# INPUT.net
KiCad netlist of a schematic drawn in Altium Designer
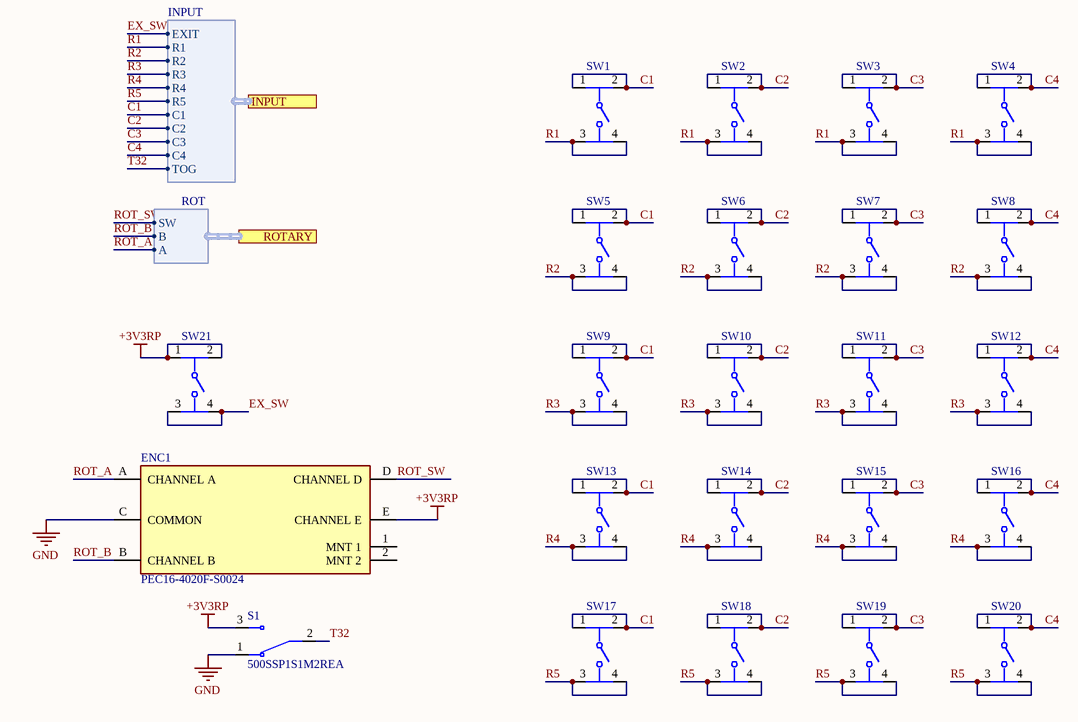
[diagram p0: INPUT.SchDoc]

(export (version "E")
  (design (tool "Eeschema 10.0.6"))
  (components
    (comp (ref "ENC1")
      (value "PEC16-4020F-S0024")
      (footprint "FP-PEC16-4020F-S0024-MFG")
      (description "ROTARY ENCODER MECHANICAL 24PPR")
      (libsource (lib "Components - 05.08.25 - 14.12") (part "CMP-07421-000008-1"))
    )
    (comp (ref "S1")
      (value "500SSP1S1M2REA")
      (footprint "SW_500SSP1S1M2REA")
      (libsource (lib "500SSP1S1M2REA") (part "500SSP1S1M2REA"))
    )
    (comp (ref "SW1")
      (value "MJTP1212A")
      (footprint "FP-MJTP1212A-MFG")
      (description "SWITCH TACTILE SPST-NO 0.05A 12V")
      (libsource (lib "Components - 05.08.25 - 14.03") (part "CMP-47024-000003-1"))
    )
    (comp (ref "SW2")
      (value "MJTP1212A")
      (footprint "FP-MJTP1212A-MFG")
      (description "SWITCH TACTILE SPST-NO 0.05A 12V")
      (libsource (lib "Components - 05.08.25 - 14.03") (part "CMP-47024-000003-1"))
    )
    (comp (ref "SW3")
      (value "MJTP1212A")
      (footprint "FP-MJTP1212A-MFG")
      (description "SWITCH TACTILE SPST-NO 0.05A 12V")
      (libsource (lib "Components - 05.08.25 - 14.03") (part "CMP-47024-000003-1"))
    )
    (comp (ref "SW4")
      (value "MJTP1212A")
      (footprint "FP-MJTP1212A-MFG")
      (description "SWITCH TACTILE SPST-NO 0.05A 12V")
      (libsource (lib "Components - 05.08.25 - 14.03") (part "CMP-47024-000003-1"))
    )
    (comp (ref "SW5")
      (value "MJTP1212A")
      (footprint "FP-MJTP1212A-MFG")
      (description "SWITCH TACTILE SPST-NO 0.05A 12V")
      (libsource (lib "Components - 05.08.25 - 14.03") (part "CMP-47024-000003-1"))
    )
    (comp (ref "SW6")
      (value "MJTP1212A")
      (footprint "FP-MJTP1212A-MFG")
      (description "SWITCH TACTILE SPST-NO 0.05A 12V")
      (libsource (lib "Components - 05.08.25 - 14.03") (part "CMP-47024-000003-1"))
    )
    (comp (ref "SW7")
      (value "MJTP1212A")
      (footprint "FP-MJTP1212A-MFG")
      (description "SWITCH TACTILE SPST-NO 0.05A 12V")
      (libsource (lib "Components - 05.08.25 - 14.03") (part "CMP-47024-000003-1"))
    )
    (comp (ref "SW8")
      (value "MJTP1212A")
      (footprint "FP-MJTP1212A-MFG")
      (description "SWITCH TACTILE SPST-NO 0.05A 12V")
      (libsource (lib "Components - 05.08.25 - 14.03") (part "CMP-47024-000003-1"))
    )
    (comp (ref "SW9")
      (value "MJTP1212A")
      (footprint "FP-MJTP1212A-MFG")
      (description "SWITCH TACTILE SPST-NO 0.05A 12V")
      (libsource (lib "Components - 05.08.25 - 14.03") (part "CMP-47024-000003-1"))
    )
    (comp (ref "SW10")
      (value "MJTP1212A")
      (footprint "FP-MJTP1212A-MFG")
      (description "SWITCH TACTILE SPST-NO 0.05A 12V")
      (libsource (lib "Components - 05.08.25 - 14.03") (part "CMP-47024-000003-1"))
    )
    (comp (ref "SW11")
      (value "MJTP1212A")
      (footprint "FP-MJTP1212A-MFG")
      (description "SWITCH TACTILE SPST-NO 0.05A 12V")
      (libsource (lib "Components - 05.08.25 - 14.03") (part "CMP-47024-000003-1"))
    )
    (comp (ref "SW12")
      (value "MJTP1212A")
      (footprint "FP-MJTP1212A-MFG")
      (description "SWITCH TACTILE SPST-NO 0.05A 12V")
      (libsource (lib "Components - 05.08.25 - 14.03") (part "CMP-47024-000003-1"))
    )
    (comp (ref "SW13")
      (value "MJTP1212A")
      (footprint "FP-MJTP1212A-MFG")
      (description "SWITCH TACTILE SPST-NO 0.05A 12V")
      (libsource (lib "Components - 05.08.25 - 14.03") (part "CMP-47024-000003-1"))
    )
    (comp (ref "SW14")
      (value "MJTP1212A")
      (footprint "FP-MJTP1212A-MFG")
      (description "SWITCH TACTILE SPST-NO 0.05A 12V")
      (libsource (lib "Components - 05.08.25 - 14.03") (part "CMP-47024-000003-1"))
    )
    (comp (ref "SW15")
      (value "MJTP1212A")
      (footprint "FP-MJTP1212A-MFG")
      (description "SWITCH TACTILE SPST-NO 0.05A 12V")
      (libsource (lib "Components - 05.08.25 - 14.03") (part "CMP-47024-000003-1"))
    )
    (comp (ref "SW16")
      (value "MJTP1212A")
      (footprint "FP-MJTP1212A-MFG")
      (description "SWITCH TACTILE SPST-NO 0.05A 12V")
      (libsource (lib "Components - 05.08.25 - 14.03") (part "CMP-47024-000003-1"))
    )
    (comp (ref "SW17")
      (value "MJTP1212A")
      (footprint "FP-MJTP1212A-MFG")
      (description "SWITCH TACTILE SPST-NO 0.05A 12V")
      (libsource (lib "Components - 05.08.25 - 14.03") (part "CMP-47024-000003-1"))
    )
    (comp (ref "SW18")
      (value "MJTP1212A")
      (footprint "FP-MJTP1212A-MFG")
      (description "SWITCH TACTILE SPST-NO 0.05A 12V")
      (libsource (lib "Components - 05.08.25 - 14.03") (part "CMP-47024-000003-1"))
    )
    (comp (ref "SW19")
      (value "MJTP1212A")
      (footprint "FP-MJTP1212A-MFG")
      (description "SWITCH TACTILE SPST-NO 0.05A 12V")
      (libsource (lib "Components - 05.08.25 - 14.03") (part "CMP-47024-000003-1"))
    )
    (comp (ref "SW20")
      (value "MJTP1212A")
      (footprint "FP-MJTP1212A-MFG")
      (description "SWITCH TACTILE SPST-NO 0.05A 12V")
      (libsource (lib "Components - 05.08.25 - 14.03") (part "CMP-47024-000003-1"))
    )
    (comp (ref "SW21")
      (value "MJTP1212A")
      (footprint "FP-MJTP1212A-MFG")
      (description "SWITCH TACTILE SPST-NO 0.05A 12V")
      (libsource (lib "Components - 05.08.25 - 14.03") (part "CMP-47024-000003-1"))
    )
  )
  (nets
    (net (code "3") (name "+3V3RP") (class "Default")
      (node (ref "ENC1") (pin "E") (pinfunction "CHANNEL_E_E") (pintype "passive"))
      (node (ref "S1") (pin "3") (pinfunction "NO_3") (pintype "passive"))
      (node (ref "SW21") (pin "1") (pinfunction "1_1") (pintype "passive"))
      (node (ref "SW21") (pin "2") (pinfunction "2_2") (pintype "passive"))
    )
    (net (code "4") (name "/C1") (class "Default")
      (node (ref "SW1") (pin "1") (pinfunction "1_1") (pintype "passive"))
      (node (ref "SW1") (pin "2") (pinfunction "2_2") (pintype "passive"))
      (node (ref "SW13") (pin "1") (pinfunction "1_1") (pintype "passive"))
      (node (ref "SW13") (pin "2") (pinfunction "2_2") (pintype "passive"))
      (node (ref "SW17") (pin "1") (pinfunction "1_1") (pintype "passive"))
      (node (ref "SW17") (pin "2") (pinfunction "2_2") (pintype "passive"))
      (node (ref "SW5") (pin "1") (pinfunction "1_1") (pintype "passive"))
      (node (ref "SW5") (pin "2") (pinfunction "2_2") (pintype "passive"))
      (node (ref "SW9") (pin "1") (pinfunction "1_1") (pintype "passive"))
      (node (ref "SW9") (pin "2") (pinfunction "2_2") (pintype "passive"))
    )
    (net (code "5") (name "/C2") (class "Default")
      (node (ref "SW10") (pin "1") (pinfunction "1_1") (pintype "passive"))
      (node (ref "SW10") (pin "2") (pinfunction "2_2") (pintype "passive"))
      (node (ref "SW14") (pin "1") (pinfunction "1_1") (pintype "passive"))
      (node (ref "SW14") (pin "2") (pinfunction "2_2") (pintype "passive"))
      (node (ref "SW18") (pin "1") (pinfunction "1_1") (pintype "passive"))
      (node (ref "SW18") (pin "2") (pinfunction "2_2") (pintype "passive"))
      (node (ref "SW2") (pin "1") (pinfunction "1_1") (pintype "passive"))
      (node (ref "SW2") (pin "2") (pinfunction "2_2") (pintype "passive"))
      (node (ref "SW6") (pin "1") (pinfunction "1_1") (pintype "passive"))
      (node (ref "SW6") (pin "2") (pinfunction "2_2") (pintype "passive"))
    )
    (net (code "6") (name "/C3") (class "Default")
      (node (ref "SW11") (pin "1") (pinfunction "1_1") (pintype "passive"))
      (node (ref "SW11") (pin "2") (pinfunction "2_2") (pintype "passive"))
      (node (ref "SW15") (pin "1") (pinfunction "1_1") (pintype "passive"))
      (node (ref "SW15") (pin "2") (pinfunction "2_2") (pintype "passive"))
      (node (ref "SW19") (pin "1") (pinfunction "1_1") (pintype "passive"))
      (node (ref "SW19") (pin "2") (pinfunction "2_2") (pintype "passive"))
      (node (ref "SW3") (pin "1") (pinfunction "1_1") (pintype "passive"))
      (node (ref "SW3") (pin "2") (pinfunction "2_2") (pintype "passive"))
      (node (ref "SW7") (pin "1") (pinfunction "1_1") (pintype "passive"))
      (node (ref "SW7") (pin "2") (pinfunction "2_2") (pintype "passive"))
    )
    (net (code "7") (name "/C4") (class "Default")
      (node (ref "SW12") (pin "1") (pinfunction "1_1") (pintype "passive"))
      (node (ref "SW12") (pin "2") (pinfunction "2_2") (pintype "passive"))
      (node (ref "SW16") (pin "1") (pinfunction "1_1") (pintype "passive"))
      (node (ref "SW16") (pin "2") (pinfunction "2_2") (pintype "passive"))
      (node (ref "SW20") (pin "1") (pinfunction "1_1") (pintype "passive"))
      (node (ref "SW20") (pin "2") (pinfunction "2_2") (pintype "passive"))
      (node (ref "SW4") (pin "1") (pinfunction "1_1") (pintype "passive"))
      (node (ref "SW4") (pin "2") (pinfunction "2_2") (pintype "passive"))
      (node (ref "SW8") (pin "1") (pinfunction "1_1") (pintype "passive"))
      (node (ref "SW8") (pin "2") (pinfunction "2_2") (pintype "passive"))
    )
    (net (code "8") (name "/EX_SW") (class "Default")
      (node (ref "SW21") (pin "3") (pinfunction "3_3") (pintype "passive"))
      (node (ref "SW21") (pin "4") (pinfunction "4_4") (pintype "passive"))
    )
    (net (code "9") (name "/R1") (class "Default")
      (node (ref "SW1") (pin "3") (pinfunction "3_3") (pintype "passive"))
      (node (ref "SW1") (pin "4") (pinfunction "4_4") (pintype "passive"))
      (node (ref "SW2") (pin "3") (pinfunction "3_3") (pintype "passive"))
      (node (ref "SW2") (pin "4") (pinfunction "4_4") (pintype "passive"))
      (node (ref "SW3") (pin "3") (pinfunction "3_3") (pintype "passive"))
      (node (ref "SW3") (pin "4") (pinfunction "4_4") (pintype "passive"))
      (node (ref "SW4") (pin "3") (pinfunction "3_3") (pintype "passive"))
      (node (ref "SW4") (pin "4") (pinfunction "4_4") (pintype "passive"))
    )
    (net (code "10") (name "/R2") (class "Default")
      (node (ref "SW5") (pin "3") (pinfunction "3_3") (pintype "passive"))
      (node (ref "SW5") (pin "4") (pinfunction "4_4") (pintype "passive"))
      (node (ref "SW6") (pin "3") (pinfunction "3_3") (pintype "passive"))
      (node (ref "SW6") (pin "4") (pinfunction "4_4") (pintype "passive"))
      (node (ref "SW7") (pin "3") (pinfunction "3_3") (pintype "passive"))
      (node (ref "SW7") (pin "4") (pinfunction "4_4") (pintype "passive"))
      (node (ref "SW8") (pin "3") (pinfunction "3_3") (pintype "passive"))
      (node (ref "SW8") (pin "4") (pinfunction "4_4") (pintype "passive"))
    )
    (net (code "11") (name "/R3") (class "Default")
      (node (ref "SW10") (pin "3") (pinfunction "3_3") (pintype "passive"))
      (node (ref "SW10") (pin "4") (pinfunction "4_4") (pintype "passive"))
      (node (ref "SW11") (pin "3") (pinfunction "3_3") (pintype "passive"))
      (node (ref "SW11") (pin "4") (pinfunction "4_4") (pintype "passive"))
      (node (ref "SW12") (pin "3") (pinfunction "3_3") (pintype "passive"))
      (node (ref "SW12") (pin "4") (pinfunction "4_4") (pintype "passive"))
      (node (ref "SW9") (pin "3") (pinfunction "3_3") (pintype "passive"))
      (node (ref "SW9") (pin "4") (pinfunction "4_4") (pintype "passive"))
    )
    (net (code "12") (name "/R4") (class "Default")
      (node (ref "SW13") (pin "3") (pinfunction "3_3") (pintype "passive"))
      (node (ref "SW13") (pin "4") (pinfunction "4_4") (pintype "passive"))
      (node (ref "SW14") (pin "3") (pinfunction "3_3") (pintype "passive"))
      (node (ref "SW14") (pin "4") (pinfunction "4_4") (pintype "passive"))
      (node (ref "SW15") (pin "3") (pinfunction "3_3") (pintype "passive"))
      (node (ref "SW15") (pin "4") (pinfunction "4_4") (pintype "passive"))
      (node (ref "SW16") (pin "3") (pinfunction "3_3") (pintype "passive"))
      (node (ref "SW16") (pin "4") (pinfunction "4_4") (pintype "passive"))
    )
    (net (code "13") (name "/R5") (class "Default")
      (node (ref "SW17") (pin "3") (pinfunction "3_3") (pintype "passive"))
      (node (ref "SW17") (pin "4") (pinfunction "4_4") (pintype "passive"))
      (node (ref "SW18") (pin "3") (pinfunction "3_3") (pintype "passive"))
      (node (ref "SW18") (pin "4") (pinfunction "4_4") (pintype "passive"))
      (node (ref "SW19") (pin "3") (pinfunction "3_3") (pintype "passive"))
      (node (ref "SW19") (pin "4") (pinfunction "4_4") (pintype "passive"))
      (node (ref "SW20") (pin "3") (pinfunction "3_3") (pintype "passive"))
      (node (ref "SW20") (pin "4") (pinfunction "4_4") (pintype "passive"))
    )
    (net (code "14") (name "/ROT_A") (class "Default")
      (node (ref "ENC1") (pin "A") (pinfunction "CHANNEL_A_A") (pintype "passive"))
    )
    (net (code "15") (name "/ROT_B") (class "Default")
      (node (ref "ENC1") (pin "B") (pinfunction "CHANNEL_B_B") (pintype "passive"))
    )
    (net (code "16") (name "/ROT_SW") (class "Default")
      (node (ref "ENC1") (pin "D") (pinfunction "CHANNEL_D_D") (pintype "passive"))
    )
    (net (code "17") (name "/T32") (class "Default")
      (node (ref "S1") (pin "2") (pinfunction "COM_2") (pintype "passive"))
    )
    (net (code "20") (name "GND") (class "Default")
      (node (ref "ENC1") (pin "C") (pinfunction "COMMON_C") (pintype "passive"))
      (node (ref "S1") (pin "1") (pinfunction "NC_1") (pintype "passive"))
    )
    (net (code "21") (name "unconnected-(ENC1-MNT_1-Pad1)") (class "Default")
      (node (ref "ENC1") (pin "1") (pinfunction "MNT_1_1") (pintype "passive"))
    )
    (net (code "22") (name "unconnected-(ENC1-MNT_2-Pad2)") (class "Default")
      (node (ref "ENC1") (pin "2") (pinfunction "MNT_2_2") (pintype "passive"))
    )
  )
)
